# energy_shield.net
KiCad netlist of a schematic drawn in EAGLE
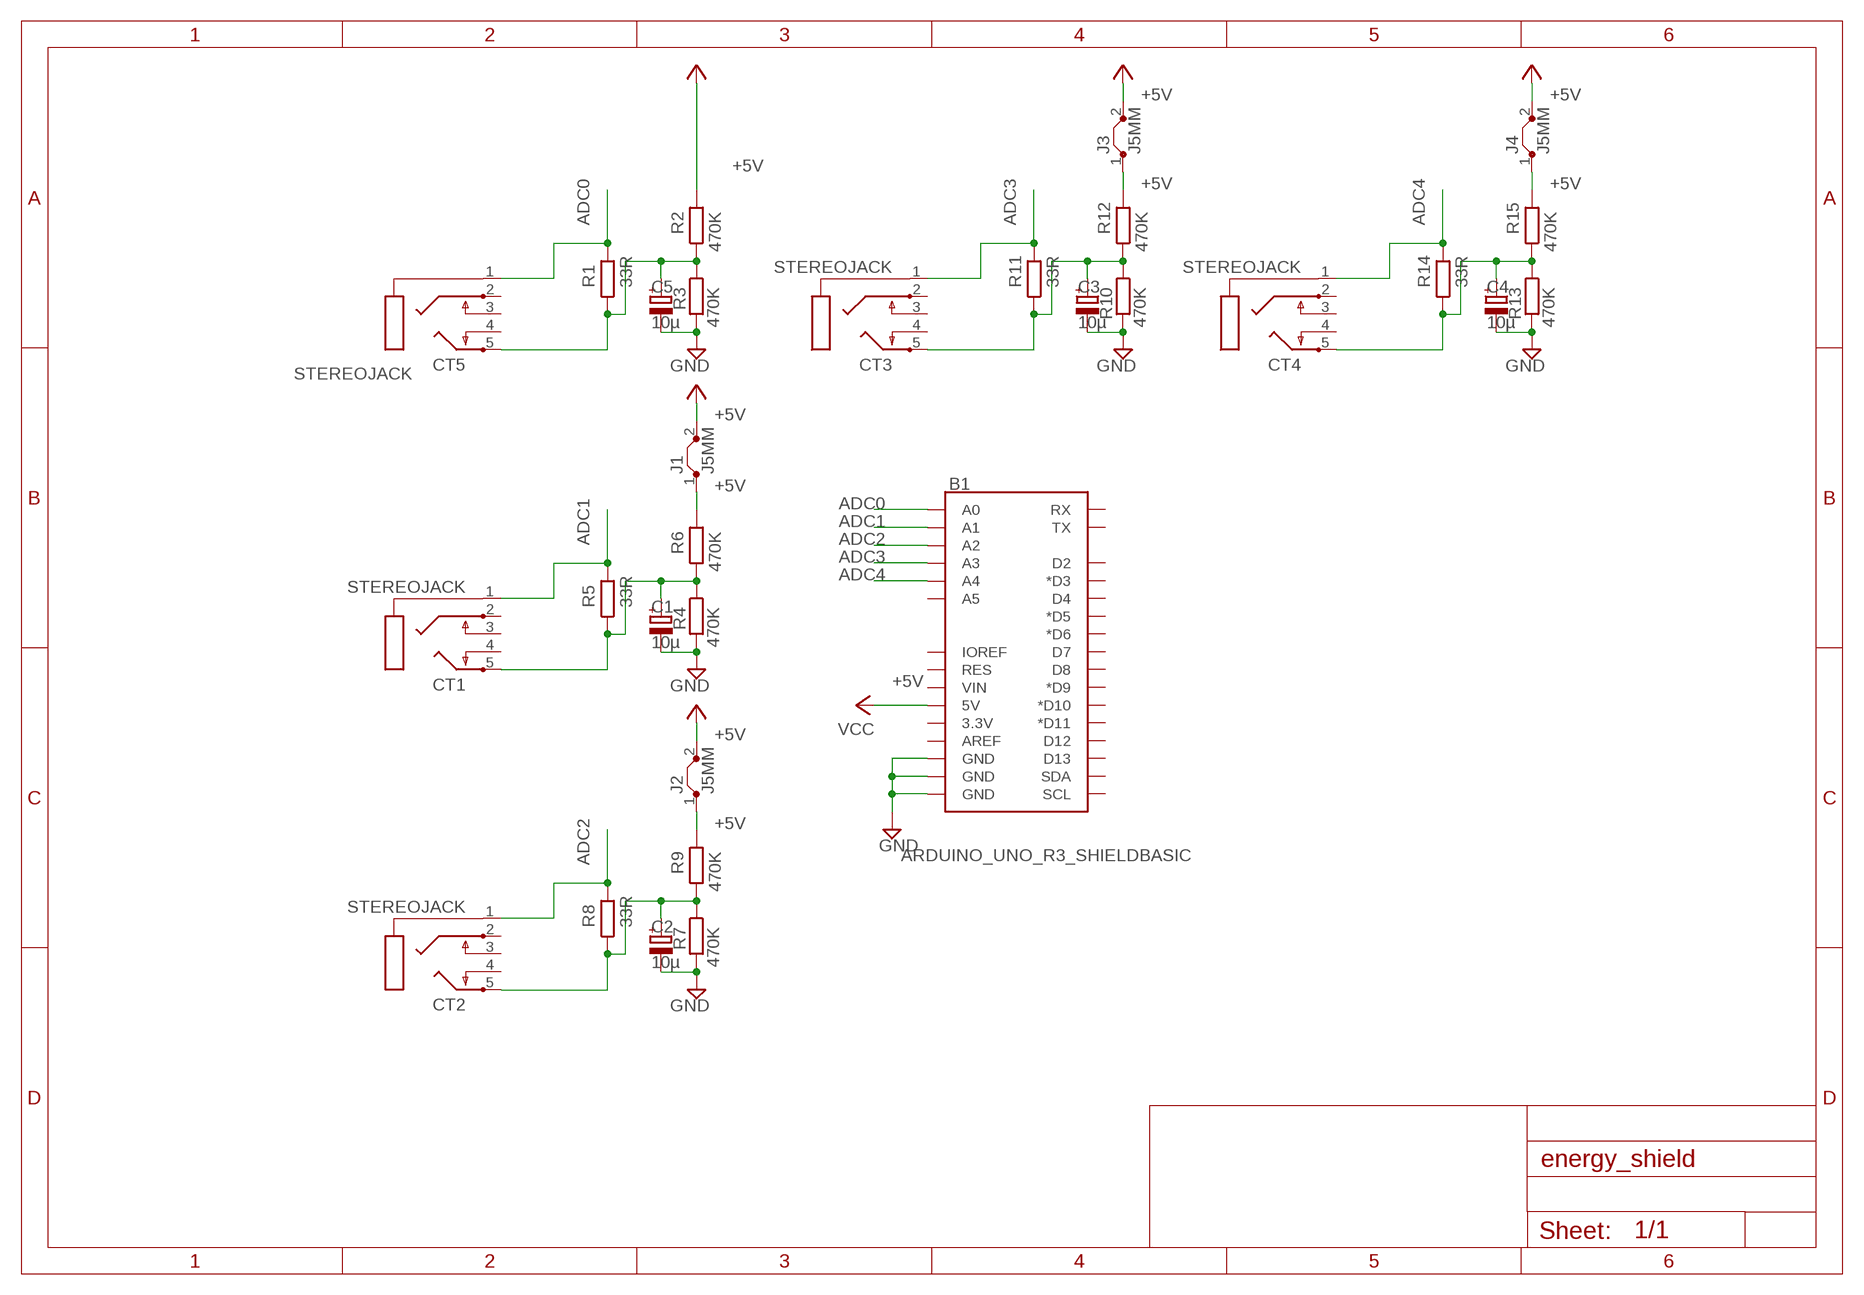
[diagram p0: schematic, sheet 1]

(export (version "E")
  (design (tool "Eeschema 10.0.6"))
  (components
    (comp (ref "B1")
      (value "ARDUINO_UNO_R3_SHIELDBASIC")
      (footprint "eagle-import:UNO_R3_SHIELD")
      (libsource (lib "eagle-import") (part "ARDUINO_UNO_R3_SHIELDBASIC"))
    )
    (comp (ref "C1")
      (value "10µ")
      (footprint "eagle-import:E1,8-4")
      (libsource (lib "eagle-import") (part "CPOL-EUE1.8-4"))
    )
    (comp (ref "C2")
      (value "10µ")
      (footprint "eagle-import:E1,8-4")
      (libsource (lib "eagle-import") (part "CPOL-EUE1.8-4"))
    )
    (comp (ref "C3")
      (value "10µ")
      (footprint "eagle-import:E1,8-4")
      (libsource (lib "eagle-import") (part "CPOL-EUE1.8-4"))
    )
    (comp (ref "C4")
      (value "10µ")
      (footprint "eagle-import:E1,8-4")
      (libsource (lib "eagle-import") (part "CPOL-EUE1.8-4"))
    )
    (comp (ref "C5")
      (value "10µ")
      (footprint "eagle-import:E1,8-4")
      (libsource (lib "eagle-import") (part "CPOL-EUE1.8-4"))
    )
    (comp (ref "CT1")
      (value "STEREOJACK")
      (footprint "eagle-import:STX3100")
      (libsource (lib "eagle-import") (part "STEREOJACK"))
    )
    (comp (ref "CT2")
      (value "STEREOJACK")
      (footprint "eagle-import:STX3100")
      (libsource (lib "eagle-import") (part "STEREOJACK"))
    )
    (comp (ref "CT3")
      (value "STEREOJACK")
      (footprint "eagle-import:STX3100")
      (libsource (lib "eagle-import") (part "STEREOJACK"))
    )
    (comp (ref "CT4")
      (value "STEREOJACK")
      (footprint "eagle-import:STX3100")
      (libsource (lib "eagle-import") (part "STEREOJACK"))
    )
    (comp (ref "CT5")
      (value "STEREOJACK")
      (footprint "eagle-import:STX3100")
      (libsource (lib "eagle-import") (part "STEREOJACK"))
    )
    (comp (ref "J1")
      (value "J5MM")
      (footprint "eagle-import:05")
      (libsource (lib "eagle-import") (part "J5MM"))
    )
    (comp (ref "J2")
      (value "J5MM")
      (footprint "eagle-import:05")
      (libsource (lib "eagle-import") (part "J5MM"))
    )
    (comp (ref "J3")
      (value "J5MM")
      (footprint "eagle-import:05")
      (libsource (lib "eagle-import") (part "J5MM"))
    )
    (comp (ref "J4")
      (value "J5MM")
      (footprint "eagle-import:05")
      (libsource (lib "eagle-import") (part "J5MM"))
    )
    (comp (ref "R1")
      (value "33R")
      (footprint "eagle-import:0204_7")
      (libsource (lib "eagle-import") (part "rcl_334_R-EU_0204/7"))
    )
    (comp (ref "R2")
      (value "470K")
      (footprint "eagle-import:0204_7")
      (libsource (lib "eagle-import") (part "rcl_334_R-EU_0204/7"))
    )
    (comp (ref "R3")
      (value "470K")
      (footprint "eagle-import:0204_7")
      (libsource (lib "eagle-import") (part "R-EU_0204/7"))
    )
    (comp (ref "R4")
      (value "470K")
      (footprint "eagle-import:0204_7")
      (libsource (lib "eagle-import") (part "R-EU_0204/7"))
    )
    (comp (ref "R5")
      (value "33R")
      (footprint "eagle-import:0204_7")
      (libsource (lib "eagle-import") (part "rcl_334_R-EU_0204/7"))
    )
    (comp (ref "R6")
      (value "470K")
      (footprint "eagle-import:0204_7")
      (libsource (lib "eagle-import") (part "R-EU_0204/7"))
    )
    (comp (ref "R7")
      (value "470K")
      (footprint "eagle-import:0204_7")
      (libsource (lib "eagle-import") (part "R-EU_0204/7"))
    )
    (comp (ref "R8")
      (value "33R")
      (footprint "eagle-import:0204_7")
      (libsource (lib "eagle-import") (part "R-EU_0204/7"))
    )
    (comp (ref "R9")
      (value "470K")
      (footprint "eagle-import:0204_7")
      (libsource (lib "eagle-import") (part "R-EU_0204/7"))
    )
    (comp (ref "R10")
      (value "470K")
      (footprint "eagle-import:0204_7")
      (libsource (lib "eagle-import") (part "R-EU_0204/7"))
    )
    (comp (ref "R11")
      (value "33R")
      (footprint "eagle-import:0204_7")
      (libsource (lib "eagle-import") (part "R-EU_0204/7"))
    )
    (comp (ref "R12")
      (value "470K")
      (footprint "eagle-import:0204_7")
      (libsource (lib "eagle-import") (part "R-EU_0204/7"))
    )
    (comp (ref "R13")
      (value "470K")
      (footprint "eagle-import:0204_7")
      (libsource (lib "eagle-import") (part "rcl_334_R-EU_0204/7"))
    )
    (comp (ref "R14")
      (value "33R")
      (footprint "eagle-import:0204_7")
      (libsource (lib "eagle-import") (part "R-EU_0204/7"))
    )
    (comp (ref "R15")
      (value "470K")
      (footprint "eagle-import:0204_7")
      (libsource (lib "eagle-import") (part "R-EU_0204/7"))
    )
  )
  (nets
    (net (code "1") (name "+5V") (class "Default")
      (node (ref "B1") (pin "5V") (pinfunction "5V_5V") (pintype "bidirectional"))
      (node (ref "J1") (pin "1") (pinfunction "1_1") (pintype "passive"))
      (node (ref "J1") (pin "2") (pinfunction "2_2") (pintype "passive"))
      (node (ref "J2") (pin "1") (pinfunction "1_1") (pintype "passive"))
      (node (ref "J2") (pin "2") (pinfunction "2_2") (pintype "passive"))
      (node (ref "J3") (pin "1") (pinfunction "1_1") (pintype "passive"))
      (node (ref "J3") (pin "2") (pinfunction "2_2") (pintype "passive"))
      (node (ref "J4") (pin "1") (pinfunction "1_1") (pintype "passive"))
      (node (ref "J4") (pin "2") (pinfunction "2_2") (pintype "passive"))
      (node (ref "R12") (pin "2") (pinfunction "2_2") (pintype "passive"))
      (node (ref "R15") (pin "2") (pinfunction "2_2") (pintype "passive"))
      (node (ref "R2") (pin "2") (pinfunction "2_2") (pintype "passive"))
      (node (ref "R6") (pin "2") (pinfunction "2_2") (pintype "passive"))
      (node (ref "R9") (pin "2") (pinfunction "2_2") (pintype "passive"))
    )
    (net (code "2") (name "/ADC0") (class "Default")
      (node (ref "B1") (pin "A0") (pinfunction "A0_A0") (pintype "bidirectional"))
      (node (ref "CT5") (pin "1") (pinfunction "1_1") (pintype "passive"))
      (node (ref "R1") (pin "2") (pinfunction "2_2") (pintype "passive"))
    )
    (net (code "3") (name "/ADC1") (class "Default")
      (node (ref "B1") (pin "A1") (pinfunction "A1_A1") (pintype "bidirectional"))
      (node (ref "CT1") (pin "1") (pinfunction "1_1") (pintype "passive"))
      (node (ref "R5") (pin "2") (pinfunction "2_2") (pintype "passive"))
    )
    (net (code "4") (name "/ADC2") (class "Default")
      (node (ref "B1") (pin "A2") (pinfunction "A2_A2") (pintype "bidirectional"))
      (node (ref "CT2") (pin "1") (pinfunction "1_1") (pintype "passive"))
      (node (ref "R8") (pin "2") (pinfunction "2_2") (pintype "passive"))
    )
    (net (code "5") (name "/ADC3") (class "Default")
      (node (ref "B1") (pin "A3") (pinfunction "A3_A3") (pintype "bidirectional"))
      (node (ref "CT3") (pin "1") (pinfunction "1_1") (pintype "passive"))
      (node (ref "R11") (pin "2") (pinfunction "2_2") (pintype "passive"))
    )
    (net (code "6") (name "/ADC4") (class "Default")
      (node (ref "B1") (pin "A4") (pinfunction "A4_A4") (pintype "bidirectional"))
      (node (ref "CT4") (pin "1") (pinfunction "1_1") (pintype "passive"))
      (node (ref "R14") (pin "2") (pinfunction "2_2") (pintype "passive"))
    )
    (net (code "7") (name "GND") (class "Default")
      (node (ref "B1") (pin "GND@0") (pinfunction "GND_GND@0") (pintype "bidirectional"))
      (node (ref "B1") (pin "GND@1") (pinfunction "GND_GND@1") (pintype "bidirectional"))
      (node (ref "B1") (pin "GND@2") (pinfunction "GND_GND@2") (pintype "bidirectional"))
      (node (ref "C1") (pin "-") (pinfunction "-_-") (pintype "passive"))
      (node (ref "C2") (pin "-") (pinfunction "-_-") (pintype "passive"))
      (node (ref "C3") (pin "-") (pinfunction "-_-") (pintype "passive"))
      (node (ref "C4") (pin "-") (pinfunction "-_-") (pintype "passive"))
      (node (ref "C5") (pin "-") (pinfunction "-_-") (pintype "passive"))
      (node (ref "R10") (pin "2") (pinfunction "2_2") (pintype "passive"))
      (node (ref "R13") (pin "2") (pinfunction "2_2") (pintype "passive"))
      (node (ref "R3") (pin "2") (pinfunction "2_2") (pintype "passive"))
      (node (ref "R4") (pin "2") (pinfunction "2_2") (pintype "passive"))
      (node (ref "R7") (pin "2") (pinfunction "2_2") (pintype "passive"))
    )
    (net (code "8") (name "Net-(C1-Pad+)") (class "Default")
      (node (ref "C1") (pin "+") (pinfunction "+_+") (pintype "passive"))
      (node (ref "CT1") (pin "5") (pinfunction "5_5") (pintype "passive"))
      (node (ref "R4") (pin "1") (pinfunction "1_1") (pintype "passive"))
      (node (ref "R5") (pin "1") (pinfunction "1_1") (pintype "passive"))
      (node (ref "R6") (pin "1") (pinfunction "1_1") (pintype "passive"))
    )
    (net (code "9") (name "Net-(C2-Pad+)") (class "Default")
      (node (ref "C2") (pin "+") (pinfunction "+_+") (pintype "passive"))
      (node (ref "CT2") (pin "5") (pinfunction "5_5") (pintype "passive"))
      (node (ref "R7") (pin "1") (pinfunction "1_1") (pintype "passive"))
      (node (ref "R8") (pin "1") (pinfunction "1_1") (pintype "passive"))
      (node (ref "R9") (pin "1") (pinfunction "1_1") (pintype "passive"))
    )
    (net (code "10") (name "Net-(C3-Pad+)") (class "Default")
      (node (ref "C3") (pin "+") (pinfunction "+_+") (pintype "passive"))
      (node (ref "CT3") (pin "5") (pinfunction "5_5") (pintype "passive"))
      (node (ref "R10") (pin "1") (pinfunction "1_1") (pintype "passive"))
      (node (ref "R11") (pin "1") (pinfunction "1_1") (pintype "passive"))
      (node (ref "R12") (pin "1") (pinfunction "1_1") (pintype "passive"))
    )
    (net (code "11") (name "Net-(C4-Pad+)") (class "Default")
      (node (ref "C4") (pin "+") (pinfunction "+_+") (pintype "passive"))
      (node (ref "CT4") (pin "5") (pinfunction "5_5") (pintype "passive"))
      (node (ref "R13") (pin "1") (pinfunction "1_1") (pintype "passive"))
      (node (ref "R14") (pin "1") (pinfunction "1_1") (pintype "passive"))
      (node (ref "R15") (pin "1") (pinfunction "1_1") (pintype "passive"))
    )
    (net (code "12") (name "Net-(C5-Pad+)") (class "Default")
      (node (ref "C5") (pin "+") (pinfunction "+_+") (pintype "passive"))
      (node (ref "CT5") (pin "5") (pinfunction "5_5") (pintype "passive"))
      (node (ref "R1") (pin "1") (pinfunction "1_1") (pintype "passive"))
      (node (ref "R2") (pin "1") (pinfunction "1_1") (pintype "passive"))
      (node (ref "R3") (pin "1") (pinfunction "1_1") (pintype "passive"))
    )
    (net (code "13") (name "unconnected-(B1-*D3-PadD3)") (class "Default")
      (node (ref "B1") (pin "D3") (pinfunction "*D3_D3") (pintype "bidirectional"))
    )
    (net (code "14") (name "unconnected-(B1-*D5-PadD5)") (class "Default")
      (node (ref "B1") (pin "D5") (pinfunction "*D5_D5") (pintype "bidirectional"))
    )
    (net (code "15") (name "unconnected-(B1-*D6-PadD6)") (class "Default")
      (node (ref "B1") (pin "D6") (pinfunction "*D6_D6") (pintype "bidirectional"))
    )
    (net (code "16") (name "unconnected-(B1-*D9-PadD9)") (class "Default")
      (node (ref "B1") (pin "D9") (pinfunction "*D9_D9") (pintype "bidirectional"))
    )
    (net (code "17") (name "unconnected-(B1-*D10-PadD10)") (class "Default")
      (node (ref "B1") (pin "D10") (pinfunction "*D10_D10") (pintype "bidirectional"))
    )
    (net (code "18") (name "unconnected-(B1-*D11-PadD11)") (class "Default")
      (node (ref "B1") (pin "D11") (pinfunction "*D11_D11") (pintype "bidirectional"))
    )
    (net (code "19") (name "unconnected-(B1-Pad3.3V)") (class "Default")
      (node (ref "B1") (pin "3.3V") (pinfunction "3.3V_3.3V") (pintype "bidirectional"))
    )
    (net (code "20") (name "unconnected-(B1-PadA5)") (class "Default")
      (node (ref "B1") (pin "A5") (pinfunction "A5_A5") (pintype "bidirectional"))
    )
    (net (code "21") (name "unconnected-(B1-PadAREF)") (class "Default")
      (node (ref "B1") (pin "AREF") (pinfunction "AREF_AREF") (pintype "bidirectional"))
    )
    (net (code "22") (name "unconnected-(B1-PadD2)") (class "Default")
      (node (ref "B1") (pin "D2") (pinfunction "D2_D2") (pintype "bidirectional"))
    )
    (net (code "23") (name "unconnected-(B1-PadD4)") (class "Default")
      (node (ref "B1") (pin "D4") (pinfunction "D4_D4") (pintype "bidirectional"))
    )
    (net (code "24") (name "unconnected-(B1-PadD7)") (class "Default")
      (node (ref "B1") (pin "D7") (pinfunction "D7_D7") (pintype "bidirectional"))
    )
    (net (code "25") (name "unconnected-(B1-PadD8)") (class "Default")
      (node (ref "B1") (pin "D8") (pinfunction "D8_D8") (pintype "bidirectional"))
    )
    (net (code "26") (name "unconnected-(B1-PadD12)") (class "Default")
      (node (ref "B1") (pin "D12") (pinfunction "D12_D12") (pintype "bidirectional"))
    )
    (net (code "27") (name "unconnected-(B1-PadD13)") (class "Default")
      (node (ref "B1") (pin "D13") (pinfunction "D13_D13") (pintype "bidirectional"))
    )
    (net (code "28") (name "unconnected-(B1-PadIOREF)") (class "Default")
      (node (ref "B1") (pin "IOREF") (pinfunction "IOREF_IOREF") (pintype "bidirectional"))
    )
    (net (code "29") (name "unconnected-(B1-PadRES)") (class "Default")
      (node (ref "B1") (pin "RES") (pinfunction "RES_RES") (pintype "bidirectional"))
    )
    (net (code "30") (name "unconnected-(B1-PadRX)") (class "Default")
      (node (ref "B1") (pin "RX") (pinfunction "RX_RX") (pintype "bidirectional"))
    )
    (net (code "31") (name "unconnected-(B1-PadSCL)") (class "Default")
      (node (ref "B1") (pin "SCL") (pinfunction "SCL_SCL") (pintype "bidirectional"))
    )
    (net (code "32") (name "unconnected-(B1-PadSDA)") (class "Default")
      (node (ref "B1") (pin "SDA") (pinfunction "SDA_SDA") (pintype "bidirectional"))
    )
    (net (code "33") (name "unconnected-(B1-PadTX)") (class "Default")
      (node (ref "B1") (pin "TX") (pinfunction "TX_TX") (pintype "bidirectional"))
    )
    (net (code "34") (name "unconnected-(B1-PadVIN)") (class "Default")
      (node (ref "B1") (pin "VIN") (pinfunction "VIN_VIN") (pintype "bidirectional"))
    )
    (net (code "35") (name "unconnected-(CT1-Pad2)") (class "Default")
      (node (ref "CT1") (pin "2") (pinfunction "2_2") (pintype "passive"))
    )
    (net (code "36") (name "unconnected-(CT1-Pad3)") (class "Default")
      (node (ref "CT1") (pin "3") (pinfunction "3_3") (pintype "passive"))
    )
    (net (code "37") (name "unconnected-(CT1-Pad4)") (class "Default")
      (node (ref "CT1") (pin "4") (pinfunction "4_4") (pintype "passive"))
    )
    (net (code "38") (name "unconnected-(CT2-Pad2)") (class "Default")
      (node (ref "CT2") (pin "2") (pinfunction "2_2") (pintype "passive"))
    )
    (net (code "39") (name "unconnected-(CT2-Pad3)") (class "Default")
      (node (ref "CT2") (pin "3") (pinfunction "3_3") (pintype "passive"))
    )
    (net (code "40") (name "unconnected-(CT2-Pad4)") (class "Default")
      (node (ref "CT2") (pin "4") (pinfunction "4_4") (pintype "passive"))
    )
    (net (code "41") (name "unconnected-(CT3-Pad2)") (class "Default")
      (node (ref "CT3") (pin "2") (pinfunction "2_2") (pintype "passive"))
    )
    (net (code "42") (name "unconnected-(CT3-Pad3)") (class "Default")
      (node (ref "CT3") (pin "3") (pinfunction "3_3") (pintype "passive"))
    )
    (net (code "43") (name "unconnected-(CT3-Pad4)") (class "Default")
      (node (ref "CT3") (pin "4") (pinfunction "4_4") (pintype "passive"))
    )
    (net (code "44") (name "unconnected-(CT4-Pad2)") (class "Default")
      (node (ref "CT4") (pin "2") (pinfunction "2_2") (pintype "passive"))
    )
    (net (code "45") (name "unconnected-(CT4-Pad3)") (class "Default")
      (node (ref "CT4") (pin "3") (pinfunction "3_3") (pintype "passive"))
    )
    (net (code "46") (name "unconnected-(CT4-Pad4)") (class "Default")
      (node (ref "CT4") (pin "4") (pinfunction "4_4") (pintype "passive"))
    )
    (net (code "47") (name "unconnected-(CT5-Pad2)") (class "Default")
      (node (ref "CT5") (pin "2") (pinfunction "2_2") (pintype "passive"))
    )
    (net (code "48") (name "unconnected-(CT5-Pad3)") (class "Default")
      (node (ref "CT5") (pin "3") (pinfunction "3_3") (pintype "passive"))
    )
    (net (code "49") (name "unconnected-(CT5-Pad4)") (class "Default")
      (node (ref "CT5") (pin "4") (pinfunction "4_4") (pintype "passive"))
    )
  )
)
